# Feeder_1U.net
KiCad netlist of a schematic drawn in Altium Designer
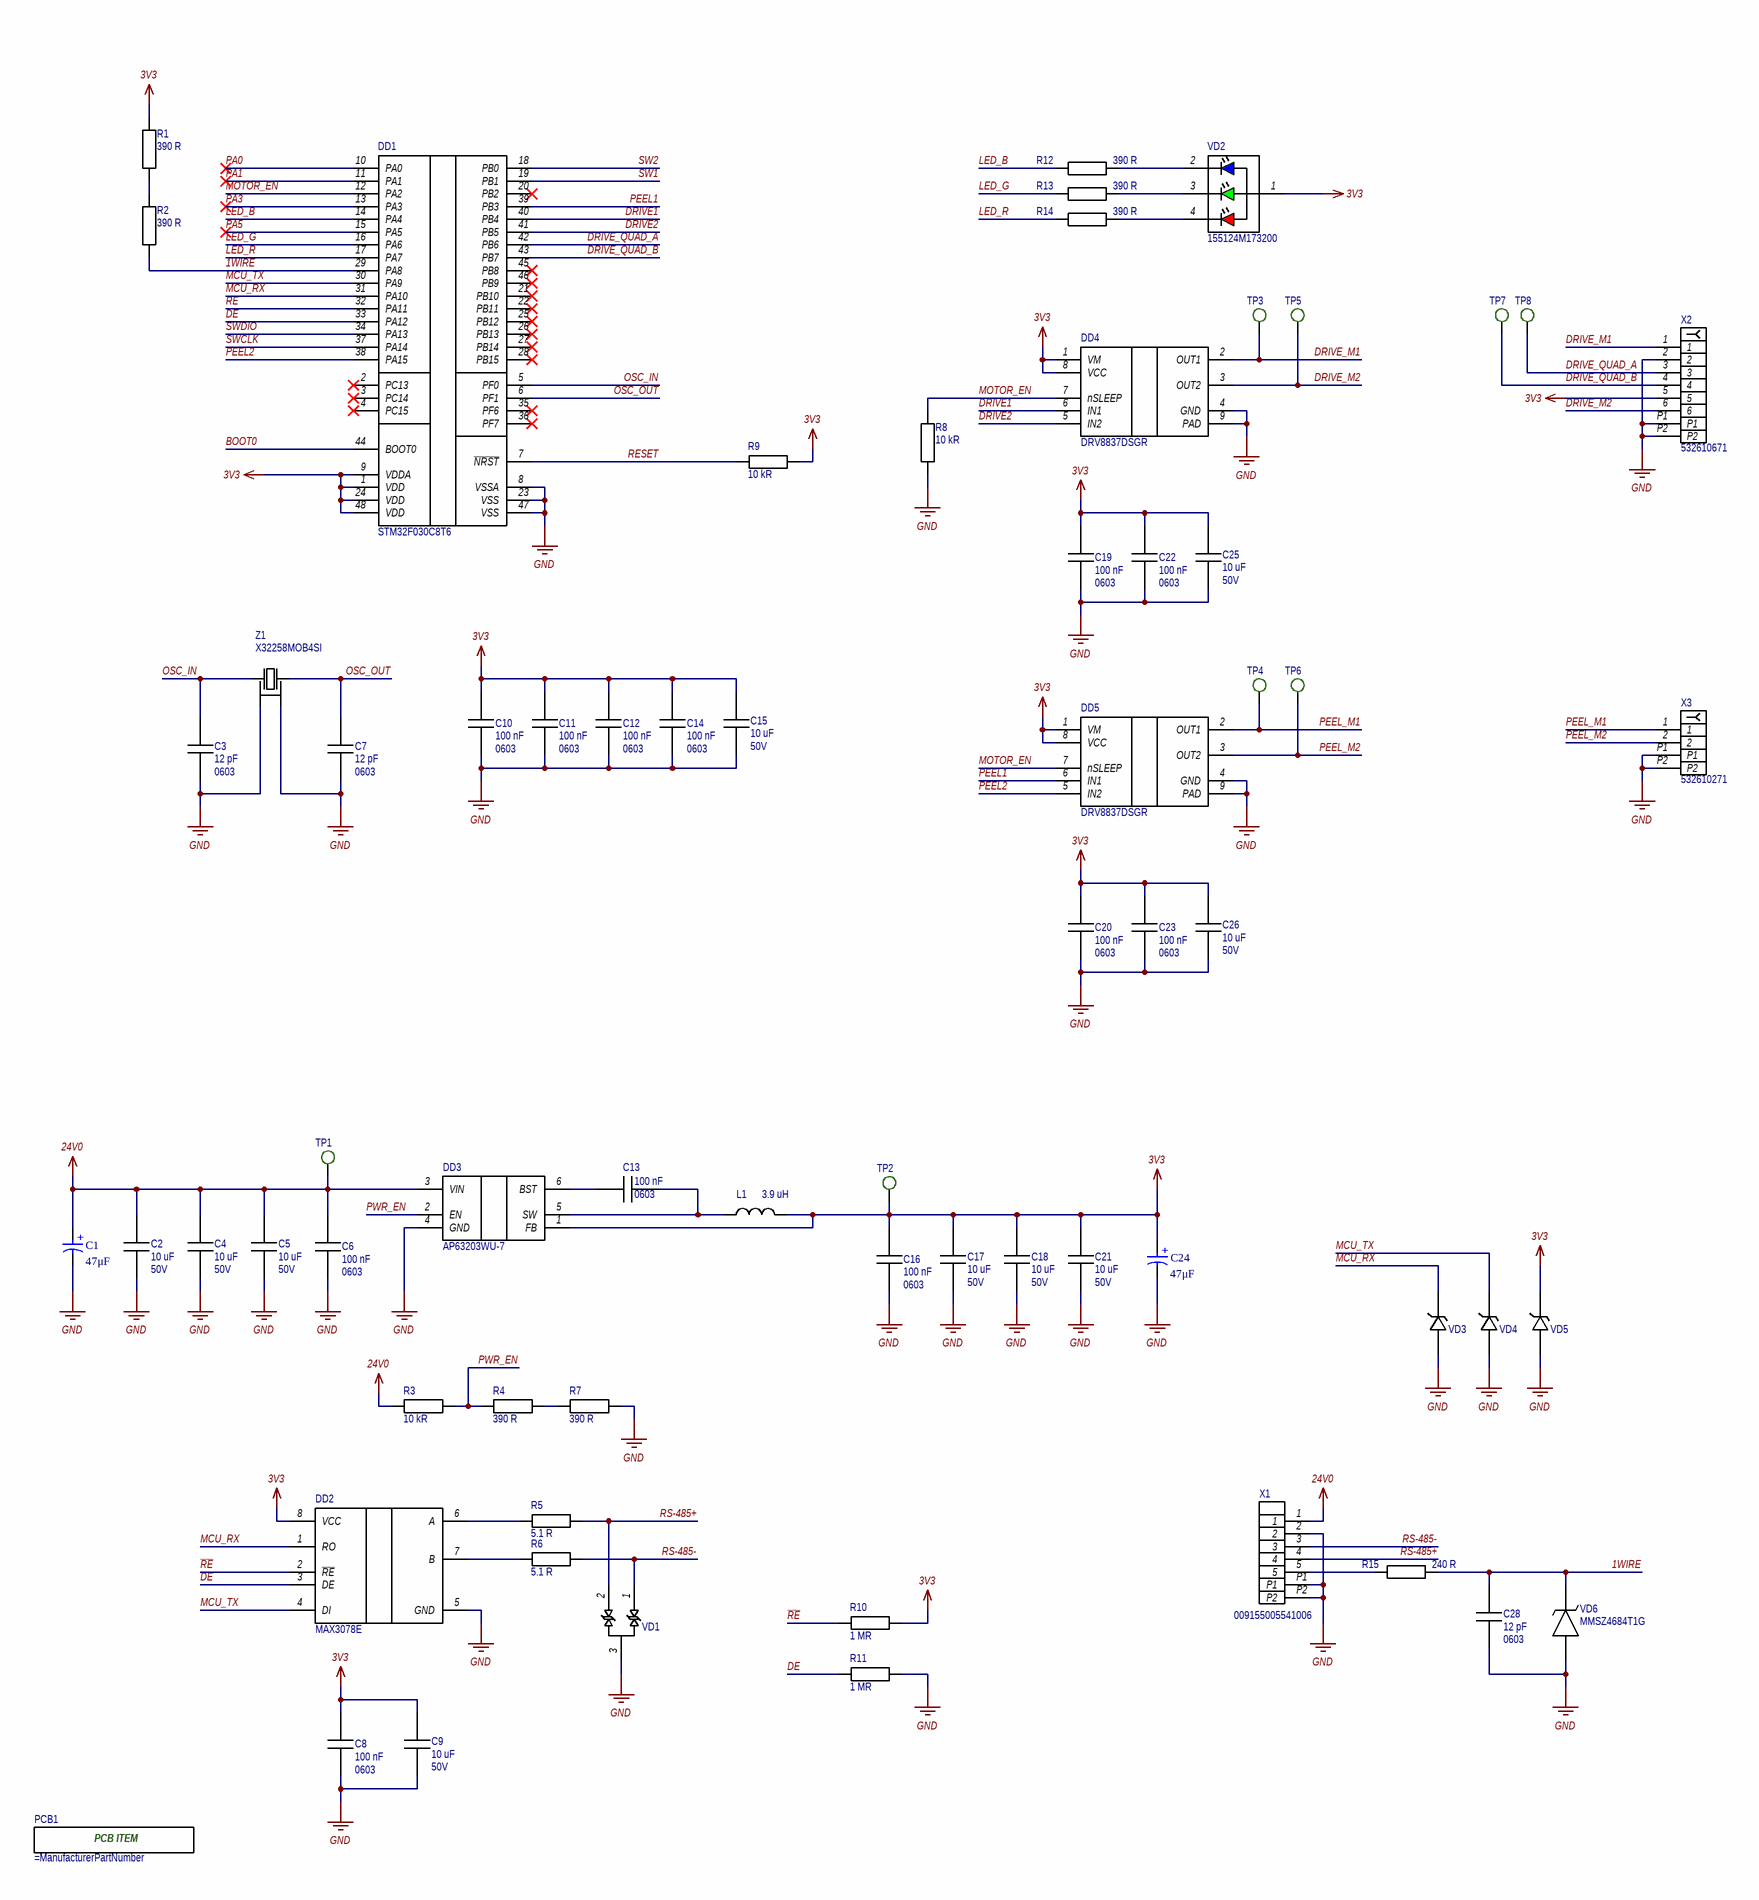
[diagram p0: Feeder_1U.SchDoc, left]
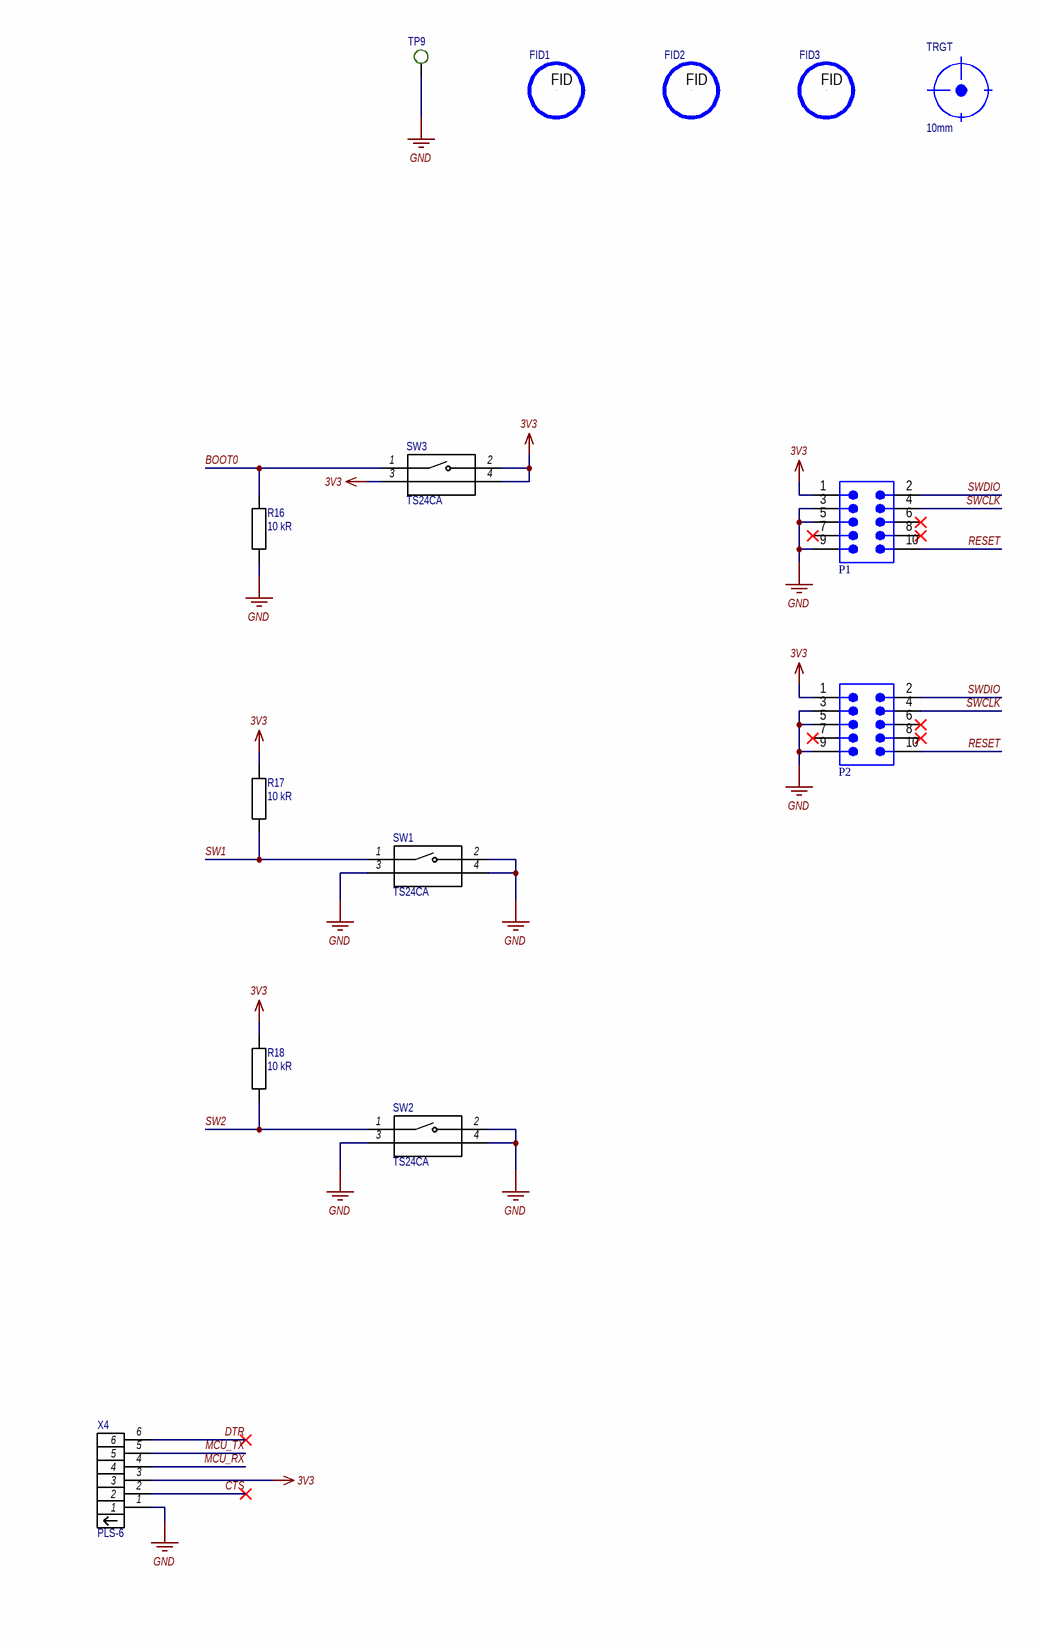
[diagram p1: Feeder_1U.SchDoc, right]

(export (version "E")
  (design (tool "Eeschema 10.0.6"))
  (components
    (comp (ref "C1")
      (value "47μF")
      (footprint "WCAP-ASLI_D6.3H7.7")
      (description "WCAP-ASLI Aluminum Electrolytic Capacitor, V-Chip, SMT, 6.3mm x 7.7mm, 47μF, 50V")
      (fields
        (field (name "MANUFACTURER PART NUMBER") "865080645012")
        (field (name "MANUFACTURER") "Wurth Elektronik")
      )
      (libsource (lib "Altium_WCAP-ASLI (rev25a)") (part "865080645012"))
    )
    (comp (ref "C2")
      (value "10 uF")
      (footprint "C_1206")
      (description "C1206 10uF X7R 50V")
      (fields
        (field (name "TOLERANCE") "±10%")
        (field (name "MANUFACTURERPARTNUMBER") "CL31B106KBHNNNE")
        (field (name "POWER/VOLTAGE") "50V")
      )
      (libsource (lib "AVERLIB_GENERAL") (part "CL31B106KBHNNNE"))
    )
    (comp (ref "C3")
      (value "12 pF")
      (footprint "C_0603")
      (description "C0603 12pF 50V")
      (fields
        (field (name "TOLERANCE") "±5%")
        (field (name "MANUFACTURERPARTNUMBER") "CC0603JRNPO9BN120")
        (field (name "КОРПУС") "0603")
      )
      (libsource (lib "AVERLIB_GENERAL") (part "CC0603JRNPO9BN120"))
    )
    (comp (ref "C4")
      (value "10 uF")
      (footprint "C_1206")
      (description "C1206 10uF X7R 50V")
      (fields
        (field (name "TOLERANCE") "±10%")
        (field (name "MANUFACTURERPARTNUMBER") "CL31B106KBHNNNE")
        (field (name "POWER/VOLTAGE") "50V")
      )
      (libsource (lib "AVERLIB_GENERAL") (part "CL31B106KBHNNNE"))
    )
    (comp (ref "C5")
      (value "10 uF")
      (footprint "C_1206")
      (description "C1206 10uF X7R 50V")
      (fields
        (field (name "TOLERANCE") "±10%")
        (field (name "MANUFACTURERPARTNUMBER") "CL31B106KBHNNNE")
        (field (name "POWER/VOLTAGE") "50V")
      )
      (libsource (lib "AVERLIB_GENERAL") (part "CL31B106KBHNNNE"))
    )
    (comp (ref "C6")
      (value "100 nF")
      (footprint "C_0603")
      (description "C0603 100nF X7R ±10% 50V")
      (fields
        (field (name "TOLERANCE") "10%")
        (field (name "MANUFACTURERPARTNUMBER") "CC0603KRX7R9BB104")
        (field (name "КОРПУС") "0603")
      )
      (libsource (lib "AVERLIB_GENERAL") (part "CC0603KRX7R9BB104"))
    )
    (comp (ref "C7")
      (value "12 pF")
      (footprint "C_0603")
      (description "C0603 12pF 50V")
      (fields
        (field (name "TOLERANCE") "±5%")
        (field (name "MANUFACTURERPARTNUMBER") "CC0603JRNPO9BN120")
        (field (name "КОРПУС") "0603")
      )
      (libsource (lib "AVERLIB_GENERAL") (part "CC0603JRNPO9BN120"))
    )
    (comp (ref "C8")
      (value "100 nF")
      (footprint "C_0603")
      (description "C0603 100nF X7R ±10% 50V")
      (fields
        (field (name "TOLERANCE") "10%")
        (field (name "MANUFACTURERPARTNUMBER") "CC0603KRX7R9BB104")
        (field (name "КОРПУС") "0603")
      )
      (libsource (lib "AVERLIB_GENERAL") (part "CC0603KRX7R9BB104"))
    )
    (comp (ref "C9")
      (value "10 uF")
      (footprint "C_1206")
      (description "C1206 10uF X7R 50V")
      (fields
        (field (name "TOLERANCE") "±10%")
        (field (name "MANUFACTURERPARTNUMBER") "CL31B106KBHNNNE")
        (field (name "POWER/VOLTAGE") "50V")
      )
      (libsource (lib "AVERLIB_GENERAL") (part "CL31B106KBHNNNE"))
    )
    (comp (ref "C10")
      (value "100 nF")
      (footprint "C_0603")
      (description "C0603 100nF X7R ±10% 50V")
      (fields
        (field (name "TOLERANCE") "10%")
        (field (name "MANUFACTURERPARTNUMBER") "CC0603KRX7R9BB104")
        (field (name "КОРПУС") "0603")
      )
      (libsource (lib "AVERLIB_GENERAL") (part "CC0603KRX7R9BB104"))
    )
    (comp (ref "C11")
      (value "100 nF")
      (footprint "C_0603")
      (description "C0603 100nF X7R ±10% 50V")
      (fields
        (field (name "TOLERANCE") "10%")
        (field (name "MANUFACTURERPARTNUMBER") "CC0603KRX7R9BB104")
        (field (name "КОРПУС") "0603")
      )
      (libsource (lib "AVERLIB_GENERAL") (part "CC0603KRX7R9BB104"))
    )
    (comp (ref "C12")
      (value "100 nF")
      (footprint "C_0603")
      (description "C0603 100nF X7R ±10% 50V")
      (fields
        (field (name "TOLERANCE") "10%")
        (field (name "MANUFACTURERPARTNUMBER") "CC0603KRX7R9BB104")
        (field (name "КОРПУС") "0603")
      )
      (libsource (lib "AVERLIB_GENERAL") (part "CC0603KRX7R9BB104"))
    )
    (comp (ref "C13")
      (value "100 nF")
      (footprint "C_0603")
      (description "C0603 100nF X7R ±10% 50V")
      (fields
        (field (name "TOLERANCE") "10%")
        (field (name "MANUFACTURERPARTNUMBER") "CC0603KRX7R9BB104")
        (field (name "КОРПУС") "0603")
      )
      (libsource (lib "AVERLIB_GENERAL") (part "CC0603KRX7R9BB104"))
    )
    (comp (ref "C14")
      (value "100 nF")
      (footprint "C_0603")
      (description "C0603 100nF X7R ±10% 50V")
      (fields
        (field (name "TOLERANCE") "10%")
        (field (name "MANUFACTURERPARTNUMBER") "CC0603KRX7R9BB104")
        (field (name "КОРПУС") "0603")
      )
      (libsource (lib "AVERLIB_GENERAL") (part "CC0603KRX7R9BB104"))
    )
    (comp (ref "C15")
      (value "10 uF")
      (footprint "C_1206")
      (description "C1206 10uF X7R 50V")
      (fields
        (field (name "TOLERANCE") "±10%")
        (field (name "MANUFACTURERPARTNUMBER") "CL31B106KBHNNNE")
        (field (name "POWER/VOLTAGE") "50V")
      )
      (libsource (lib "AVERLIB_GENERAL") (part "CL31B106KBHNNNE"))
    )
    (comp (ref "C16")
      (value "100 nF")
      (footprint "C_0603")
      (description "C0603 100nF X7R ±10% 50V")
      (fields
        (field (name "TOLERANCE") "10%")
        (field (name "MANUFACTURERPARTNUMBER") "CC0603KRX7R9BB104")
        (field (name "КОРПУС") "0603")
      )
      (libsource (lib "AVERLIB_GENERAL") (part "CC0603KRX7R9BB104"))
    )
    (comp (ref "C17")
      (value "10 uF")
      (footprint "C_1206")
      (description "C1206 10uF X7R 50V")
      (fields
        (field (name "TOLERANCE") "±10%")
        (field (name "MANUFACTURERPARTNUMBER") "CL31B106KBHNNNE")
        (field (name "POWER/VOLTAGE") "50V")
      )
      (libsource (lib "AVERLIB_GENERAL") (part "CL31B106KBHNNNE"))
    )
    (comp (ref "C18")
      (value "10 uF")
      (footprint "C_1206")
      (description "C1206 10uF X7R 50V")
      (fields
        (field (name "TOLERANCE") "±10%")
        (field (name "MANUFACTURERPARTNUMBER") "CL31B106KBHNNNE")
        (field (name "POWER/VOLTAGE") "50V")
      )
      (libsource (lib "AVERLIB_GENERAL") (part "CL31B106KBHNNNE"))
    )
    (comp (ref "C19")
      (value "100 nF")
      (footprint "C_0603")
      (description "C0603 100nF X7R ±10% 50V")
      (fields
        (field (name "TOLERANCE") "10%")
        (field (name "MANUFACTURERPARTNUMBER") "CC0603KRX7R9BB104")
        (field (name "КОРПУС") "0603")
      )
      (libsource (lib "AVERLIB_GENERAL") (part "CC0603KRX7R9BB104"))
    )
    (comp (ref "C20")
      (value "100 nF")
      (footprint "C_0603")
      (description "C0603 100nF X7R ±10% 50V")
      (fields
        (field (name "TOLERANCE") "10%")
        (field (name "MANUFACTURERPARTNUMBER") "CC0603KRX7R9BB104")
        (field (name "КОРПУС") "0603")
      )
      (libsource (lib "AVERLIB_GENERAL") (part "CC0603KRX7R9BB104"))
    )
    (comp (ref "C21")
      (value "10 uF")
      (footprint "C_1206")
      (description "C1206 10uF X7R 50V")
      (fields
        (field (name "TOLERANCE") "±10%")
        (field (name "MANUFACTURERPARTNUMBER") "CL31B106KBHNNNE")
        (field (name "POWER/VOLTAGE") "50V")
      )
      (libsource (lib "AVERLIB_GENERAL") (part "CL31B106KBHNNNE"))
    )
    (comp (ref "C22")
      (value "100 nF")
      (footprint "C_0603")
      (description "C0603 100nF X7R ±10% 50V")
      (fields
        (field (name "TOLERANCE") "10%")
        (field (name "MANUFACTURERPARTNUMBER") "CC0603KRX7R9BB104")
        (field (name "КОРПУС") "0603")
      )
      (libsource (lib "AVERLIB_GENERAL") (part "CC0603KRX7R9BB104"))
    )
    (comp (ref "C23")
      (value "100 nF")
      (footprint "C_0603")
      (description "C0603 100nF X7R ±10% 50V")
      (fields
        (field (name "TOLERANCE") "10%")
        (field (name "MANUFACTURERPARTNUMBER") "CC0603KRX7R9BB104")
        (field (name "КОРПУС") "0603")
      )
      (libsource (lib "AVERLIB_GENERAL") (part "CC0603KRX7R9BB104"))
    )
    (comp (ref "C24")
      (value "47μF")
      (footprint "WCAP-ASLI_D6.3H7.7")
      (description "WCAP-ASLI Aluminum Electrolytic Capacitor, V-Chip, SMT, 6.3mm x 7.7mm, 47μF, 50V")
      (fields
        (field (name "MANUFACTURER PART NUMBER") "865080645012")
        (field (name "MANUFACTURER") "Wurth Elektronik")
      )
      (libsource (lib "Altium_WCAP-ASLI (rev25a)") (part "865080645012"))
    )
    (comp (ref "C25")
      (value "10 uF")
      (footprint "C_1206")
      (description "C1206 10uF X7R 50V")
      (fields
        (field (name "TOLERANCE") "±10%")
        (field (name "MANUFACTURERPARTNUMBER") "CL31B106KBHNNNE")
        (field (name "POWER/VOLTAGE") "50V")
      )
      (libsource (lib "AVERLIB_GENERAL") (part "CL31B106KBHNNNE"))
    )
    (comp (ref "C26")
      (value "10 uF")
      (footprint "C_1206")
      (description "C1206 10uF X7R 50V")
      (fields
        (field (name "TOLERANCE") "±10%")
        (field (name "MANUFACTURERPARTNUMBER") "CL31B106KBHNNNE")
        (field (name "POWER/VOLTAGE") "50V")
      )
      (libsource (lib "AVERLIB_GENERAL") (part "CL31B106KBHNNNE"))
    )
    (comp (ref "C28")
      (value "12 pF")
      (footprint "C_0603")
      (description "C0603 12pF 50V")
      (fields
        (field (name "TOLERANCE") "±5%")
        (field (name "MANUFACTURERPARTNUMBER") "CC0603JRNPO9BN120")
        (field (name "КОРПУС") "0603")
      )
      (libsource (lib "AVERLIB_GENERAL") (part "CC0603JRNPO9BN120"))
    )
    (comp (ref "DD1")
      (value "STM32F030C8T6")
      (footprint "QFP-48")
      (description "MCU STM32 ARM Cortex-M0 32Bit 48MHz")
      (fields (field (name "MANUFACTURER") "STM"))
      (libsource (lib "AVERLIB_GENERAL") (part "STM32F030C8T6"))
    )
    (comp (ref "DD2")
      (value "MAX3078E")
      (footprint "SOP8")
      (description "RS-485 Line Driver and Receiver")
      (fields (field (name "MANUFACTURERPARTNUMBER") "MAX3078EESA+T") (field (name "MANUFACTURER") "Maxim"))
      (libsource (lib "AVERLIB_GENERAL") (part "MAX3078E"))
    )
    (comp (ref "DD3")
      (value "AP63203WU-7")
      (footprint "TSOT-23-6")
      (description "DC-DC Stepdown Fixed 2A 3.3V")
      (fields (field (name "MANUFACTURER") "Diodes"))
      (libsource (lib "AVERLIB_GENERAL") (part "AP63203WU-7"))
    )
    (comp (ref "DD4")
      (value "DRV8837DSGR")
      (footprint "WSON-8")
      (description "Motor Driver 1.8A")
      (fields (field (name "MANUFACTURER") "TI"))
      (libsource (lib "AVERLIB_GENERAL") (part "DRV8837DSGR"))
    )
    (comp (ref "DD5")
      (value "DRV8837DSGR")
      (footprint "WSON-8")
      (description "Motor Driver 1.8A")
      (fields (field (name "MANUFACTURER") "TI"))
      (libsource (lib "AVERLIB_GENERAL") (part "DRV8837DSGR"))
    )
    (comp (ref "FID1")
      (value "FID")
      (footprint "FIDUCIAL")
      (libsource (lib "AVERLIB_GENERAL") (part "FIDUCIAL"))
    )
    (comp (ref "FID2")
      (value "FID")
      (footprint "FIDUCIAL")
      (libsource (lib "AVERLIB_GENERAL") (part "FIDUCIAL"))
    )
    (comp (ref "FID3")
      (value "FID")
      (footprint "FIDUCIAL")
      (libsource (lib "AVERLIB_GENERAL") (part "FIDUCIAL"))
    )
    (comp (ref "L1")
      (value "3.9 uH")
      (footprint "IND_SDR0805")
      (description "L 3.9uH  4.4А")
      (fields (field (name "TOLERANCE") "±20%") (field (name "MANUFACTURERPARTNUMBER") "SDR0805-3R9ML"))
      (libsource (lib "AVERLIB_GENERAL") (part "SDR0805-3R9ML"))
    )
    (comp (ref "P1")
      (value "62101021021")
      (footprint "62101021021")
      (description "WR-PHD Pin Header, SMT, Vertical, pitch 1.27mm, 2 Row, 10P")
      (fields (field (name "MANUFACTURER") "Wurth Elektronik"))
      (libsource (lib "Altium_WR-PHD (rev24a)") (part "62101021021"))
    )
    (comp (ref "P2")
      (value "62101021021")
      (footprint "62101021021")
      (description "WR-PHD Pin Header, SMT, Vertical, pitch 1.27mm, 2 Row, 10P")
      (fields (field (name "MANUFACTURER") "Wurth Elektronik"))
      (libsource (lib "Altium_WR-PHD (rev24a)") (part "62101021021"))
    )
    (comp (ref "PCB1")
      (value "~")
      (description "!PCB")
      (fields (field (name "MANUFACTURER") "NOVA"))
      (libsource (lib "AVERLIB_GENERAL") (part "!PCB"))
    )
    (comp (ref "R1")
      (value "390 R")
      (footprint "R_0603")
      (description "R0603 390±1% 50V")
      (fields (field (name "TOLERANCE") "±1%") (field (name "MANUFACTURERPARTNUMBER") "RC0603FR-07390RL"))
      (libsource (lib "AVERLIB_GENERAL") (part "RC0603FR-07390RL"))
    )
    (comp (ref "R2")
      (value "390 R")
      (footprint "R_0603")
      (description "R0603 390±1% 50V")
      (fields (field (name "TOLERANCE") "±1%") (field (name "MANUFACTURERPARTNUMBER") "RC0603FR-07390RL"))
      (libsource (lib "AVERLIB_GENERAL") (part "RC0603FR-07390RL"))
    )
    (comp (ref "R3")
      (value "10 kR")
      (footprint "R_0603")
      (description "R0603 10k±1% 50V")
      (fields (field (name "TOLERANCE") "±1%") (field (name "MANUFACTURERPARTNUMBER") "RC0603FR-0710KL"))
      (libsource (lib "AVERLIB_GENERAL") (part "RC0603FR-0710KL"))
    )
    (comp (ref "R4")
      (value "390 R")
      (footprint "R_0603")
      (description "R0603 390±1% 50V")
      (fields (field (name "TOLERANCE") "±1%") (field (name "MANUFACTURERPARTNUMBER") "RC0603FR-07390RL"))
      (libsource (lib "AVERLIB_GENERAL") (part "RC0603FR-07390RL"))
    )
    (comp (ref "R5")
      (value "5.1 R")
      (footprint "R_0603")
      (description "R0603 5R1±1% 50V")
      (fields (field (name "TOLERANCE") "±1%") (field (name "MANUFACTURERPARTNUMBER") "RC0603FR-075R1L"))
      (libsource (lib "AVERLIB_GENERAL") (part "RC0603FR-075R1L"))
    )
    (comp (ref "R6")
      (value "5.1 R")
      (footprint "R_0603")
      (description "R0603 5R1±1% 50V")
      (fields (field (name "TOLERANCE") "±1%") (field (name "MANUFACTURERPARTNUMBER") "RC0603FR-075R1L"))
      (libsource (lib "AVERLIB_GENERAL") (part "RC0603FR-075R1L"))
    )
    (comp (ref "R7")
      (value "390 R")
      (footprint "R_0603")
      (description "R0603 390±1% 50V")
      (fields (field (name "TOLERANCE") "±1%") (field (name "MANUFACTURERPARTNUMBER") "RC0603FR-07390RL"))
      (libsource (lib "AVERLIB_GENERAL") (part "RC0603FR-07390RL"))
    )
    (comp (ref "R8")
      (value "10 kR")
      (footprint "R_0603")
      (description "R0603 10k±1% 50V")
      (fields (field (name "TOLERANCE") "±1%") (field (name "MANUFACTURERPARTNUMBER") "RC0603FR-0710KL"))
      (libsource (lib "AVERLIB_GENERAL") (part "RC0603FR-0710KL"))
    )
    (comp (ref "R9")
      (value "10 kR")
      (footprint "R_0603")
      (description "R0603 10k±1% 50V")
      (fields (field (name "TOLERANCE") "±1%") (field (name "MANUFACTURERPARTNUMBER") "RC0603FR-0710KL"))
      (libsource (lib "AVERLIB_GENERAL") (part "RC0603FR-0710KL"))
    )
    (comp (ref "R10")
      (value "1 MR")
      (footprint "R_0603")
      (description "R0603 1M±1% 50V")
      (fields (field (name "TOLERANCE") "±1%") (field (name "MANUFACTURERPARTNUMBER") "RC0603FR-071ML"))
      (libsource (lib "AVERLIB_GENERAL") (part "RC0603FR-071ML"))
    )
    (comp (ref "R11")
      (value "1 MR")
      (footprint "R_0603")
      (description "R0603 1M±1% 50V")
      (fields (field (name "TOLERANCE") "±1%") (field (name "MANUFACTURERPARTNUMBER") "RC0603FR-071ML"))
      (libsource (lib "AVERLIB_GENERAL") (part "RC0603FR-071ML"))
    )
    (comp (ref "R12")
      (value "390 R")
      (footprint "R_0603")
      (description "R0603 390±1% 50V")
      (fields (field (name "TOLERANCE") "±1%") (field (name "MANUFACTURERPARTNUMBER") "RC0603FR-07390RL"))
      (libsource (lib "AVERLIB_GENERAL") (part "RC0603FR-07390RL"))
    )
    (comp (ref "R13")
      (value "390 R")
      (footprint "R_0603")
      (description "R0603 390±1% 50V")
      (fields (field (name "TOLERANCE") "±1%") (field (name "MANUFACTURERPARTNUMBER") "RC0603FR-07390RL"))
      (libsource (lib "AVERLIB_GENERAL") (part "RC0603FR-07390RL"))
    )
    (comp (ref "R14")
      (value "390 R")
      (footprint "R_0603")
      (description "R0603 390±1% 50V")
      (fields (field (name "TOLERANCE") "±1%") (field (name "MANUFACTURERPARTNUMBER") "RC0603FR-07390RL"))
      (libsource (lib "AVERLIB_GENERAL") (part "RC0603FR-07390RL"))
    )
    (comp (ref "R15")
      (value "240 R")
      (footprint "R_0603")
      (description "R0603 240±1% 50V")
      (fields (field (name "TOLERANCE") "±1%") (field (name "MANUFACTURERPARTNUMBER") "RC0603FR-07240RL"))
      (libsource (lib "AVERLIB_GENERAL") (part "RC0603FR-07240RL"))
    )
    (comp (ref "R16")
      (value "10 kR")
      (footprint "R_0603")
      (description "R0603 10k±1% 50V")
      (fields (field (name "TOLERANCE") "±1%") (field (name "MANUFACTURERPARTNUMBER") "RC0603FR-0710KL"))
      (libsource (lib "AVERLIB_GENERAL") (part "RC0603FR-0710KL"))
    )
    (comp (ref "R17")
      (value "10 kR")
      (footprint "R_0603")
      (description "R0603 10k±1% 50V")
      (fields (field (name "TOLERANCE") "±1%") (field (name "MANUFACTURERPARTNUMBER") "RC0603FR-0710KL"))
      (libsource (lib "AVERLIB_GENERAL") (part "RC0603FR-0710KL"))
    )
    (comp (ref "R18")
      (value "10 kR")
      (footprint "R_0603")
      (description "R0603 10k±1% 50V")
      (fields (field (name "TOLERANCE") "±1%") (field (name "MANUFACTURERPARTNUMBER") "RC0603FR-0710KL"))
      (libsource (lib "AVERLIB_GENERAL") (part "RC0603FR-0710KL"))
    )
    (comp (ref "SW1")
      (value "TS24CA")
      (footprint "TS24CA")
      (description "Switch Tacticle (button) 4.7x1.9mm angle")
      (fields (field (name "MANUFACTURER") "Shou HAN"))
      (libsource (lib "AVERLIB_GENERAL") (part "TS24CA"))
    )
    (comp (ref "SW2")
      (value "TS24CA")
      (footprint "TS24CA")
      (description "Switch Tacticle (button) 4.7x1.9mm angle")
      (fields (field (name "MANUFACTURER") "Shou HAN"))
      (libsource (lib "AVERLIB_GENERAL") (part "TS24CA"))
    )
    (comp (ref "SW3")
      (value "TS24CA")
      (footprint "TS24CA")
      (description "Switch Tacticle (button) 4.7x1.9mm angle")
      (fields (field (name "MANUFACTURER") "Shou HAN"))
      (libsource (lib "AVERLIB_GENERAL") (part "TS24CA"))
    )
    (comp (ref "TP1")
      (value "*")
      (footprint "TEST POINT ROUND")
      (description "Test Point")
      (libsource (lib "AVERLIB_GENERAL") (part "TEST POINT"))
    )
    (comp (ref "TP2")
      (value "*")
      (footprint "TEST POINT ROUND")
      (description "Test Point")
      (libsource (lib "AVERLIB_GENERAL") (part "TEST POINT"))
    )
    (comp (ref "TP3")
      (value "*")
      (footprint "TEST POINT ROUND")
      (description "Test Point")
      (libsource (lib "AVERLIB_GENERAL") (part "TEST POINT"))
    )
    (comp (ref "TP4")
      (value "*")
      (footprint "TEST POINT ROUND")
      (description "Test Point")
      (libsource (lib "AVERLIB_GENERAL") (part "TEST POINT"))
    )
    (comp (ref "TP5")
      (value "*")
      (footprint "TEST POINT ROUND")
      (description "Test Point")
      (libsource (lib "AVERLIB_GENERAL") (part "TEST POINT"))
    )
    (comp (ref "TP6")
      (value "*")
      (footprint "TEST POINT ROUND")
      (description "Test Point")
      (libsource (lib "AVERLIB_GENERAL") (part "TEST POINT"))
    )
    (comp (ref "TP7")
      (value "*")
      (footprint "TEST POINT ROUND")
      (description "Test Point")
      (libsource (lib "AVERLIB_GENERAL") (part "TEST POINT"))
    )
    (comp (ref "TP8")
      (value "*")
      (footprint "TEST POINT ROUND")
      (description "Test Point")
      (libsource (lib "AVERLIB_GENERAL") (part "TEST POINT"))
    )
    (comp (ref "TP9")
      (value "*")
      (footprint "TEST POINT ROUND")
      (description "Test Point")
      (libsource (lib "AVERLIB_GENERAL") (part "TEST POINT"))
    )
    (comp (ref "TRGT")
      (value "10mm")
      (footprint "PrinterTarget")
      (description "SMD Printer calibration PCB thikness target")
      (libsource (lib "AVERLIB_GENERAL") (part "PrinterTarget_10mm"))
    )
    (comp (ref "VD1")
      (value "SM712")
      (footprint "SOT23")
      (description "ESD Suppressor Diode TVS RS485")
      (fields (field (name "MANUFACTURER") "TECH PUBLIC"))
      (libsource (lib "AVERLIB_GENERAL") (part "SM712"))
    )
    (comp (ref "VD2")
      (value "155124M173200")
      (footprint "LED_3210_RGB_SIDE")
      (description "LED RGB 3210 ANGLE")
      (fields (field (name "MANUFACTURER") "Wurth Elec") (field (name "ANALOGPARTNUMBER") "MHS110FRGBCT"))
      (libsource (lib "AVERLIB_GENERAL") (part "155124M173200"))
    )
    (comp (ref "VD3")
      (value "PESD3V3S1UL,315")
      (footprint "DFN1006-2_(SOD882)")
      (description "ESD Suppressor Diode TVS 3V3")
      (fields (field (name "MANUFACTURER") "Nexperia"))
      (libsource (lib "AVERLIB_GENERAL") (part "PESD3V3S1UL,315"))
    )
    (comp (ref "VD4")
      (value "PESD3V3S1UL,315")
      (footprint "DFN1006-2_(SOD882)")
      (description "ESD Suppressor Diode TVS 3V3")
      (fields (field (name "MANUFACTURER") "Nexperia"))
      (libsource (lib "AVERLIB_GENERAL") (part "PESD3V3S1UL,315"))
    )
    (comp (ref "VD5")
      (value "PESD3V3S1UL,315")
      (footprint "DFN1006-2_(SOD882)")
      (description "ESD Suppressor Diode TVS 3V3")
      (fields (field (name "MANUFACTURER") "Nexperia"))
      (libsource (lib "AVERLIB_GENERAL") (part "PESD3V3S1UL,315"))
    )
    (comp (ref "VD6")
      (value "MMSZ4684T1G")
      (footprint "SOD-123")
      (description "Zener Diode 3.3V SOD-123")
      (fields (field (name "MANUFACTURER") "onsemi"))
      (libsource (lib "AVERLIB_GENERAL") (part "MMSZ4684T1G"))
    )
    (comp (ref "X1")
      (value "009155005541006")
      (footprint "009155005541006")
      (description "Connector, пружинный контакт для аккумулятора, шаг 2.5мм")
      (fields (field (name "MANUFACTURER") "Kyocera AVX"))
      (libsource (lib "AVERLIB_GENERAL") (part "009155005541006"))
    )
    (comp (ref "X2")
      (value "532610671")
      (footprint "532610671")
      (description "Connector Molex PicoBlade SMD 6pin")
      (fields (field (name "MANUFACTURER") "MOLEX"))
      (libsource (lib "AVERLIB_GENERAL") (part "532610671"))
    )
    (comp (ref "X3")
      (value "532610271")
      (footprint "532610271")
      (description "Connector Molex PicoBlade SMD 2pin")
      (fields (field (name "MANUFACTURER") "MOLEX"))
      (libsource (lib "AVERLIB_GENERAL") (part "532610271"))
    )
    (comp (ref "X4")
      (value "PLS-6")
      (footprint "PLS-6-3D")
      (description "Header, 6-Pin")
      (libsource (lib "AVERLIB_GENERAL") (part "PLS-6"))
    )
    (comp (ref "Z1")
      (value "X32258MOB4SI")
      (footprint "SMD3225")
      (description "Crystal 8MHz 12pF")
      (fields (field (name "TOLERANCE") "±10ppm") (field (name "MANUFACTURER") "YXC Crystal Oscillators"))
      (libsource (lib "AVERLIB_GENERAL") (part "X32258MOB4SI"))
    )
  )
  (nets
    (net (code "1") (name "/1WIRE") (class "Default")
      (node (ref "C28") (pin "1") (pinfunction "1_1") (pintype "passive"))
      (node (ref "DD1") (pin "29") (pinfunction "PA8_29") (pintype "passive"))
      (node (ref "R15") (pin "2") (pinfunction "2_2") (pintype "passive"))
      (node (ref "R2") (pin "2") (pinfunction "2_2") (pintype "passive"))
      (node (ref "VD6") (pin "1") (pinfunction "K_1") (pintype "passive"))
    )
    (net (code "2") (name "/BOOT0") (class "Default")
      (node (ref "DD1") (pin "44") (pinfunction "BOOT0_44") (pintype "passive"))
      (node (ref "R16") (pin "2") (pinfunction "2_2") (pintype "passive"))
      (node (ref "SW3") (pin "1") (pinfunction "COM_1_1") (pintype "passive"))
    )
    (net (code "3") (name "/CTS") (class "Default")
      (node (ref "X4") (pin "2") (pinfunction "2_2") (pintype "passive+no_connect"))
    )
    (net (code "4") (name "/DE") (class "Default")
      (node (ref "DD1") (pin "33") (pinfunction "PA12_33") (pintype "passive"))
      (node (ref "DD2") (pin "3") (pinfunction "DE_3") (pintype "passive"))
      (node (ref "R11") (pin "1") (pinfunction "1_1") (pintype "passive"))
    )
    (net (code "5") (name "/DRIVE1") (class "Default")
      (node (ref "DD1") (pin "40") (pinfunction "PB4_40") (pintype "passive"))
      (node (ref "DD4") (pin "6") (pinfunction "IN1_6") (pintype "passive"))
    )
    (net (code "6") (name "/DRIVE2") (class "Default")
      (node (ref "DD1") (pin "41") (pinfunction "PB5_41") (pintype "passive"))
      (node (ref "DD4") (pin "5") (pinfunction "IN2_5") (pintype "passive"))
    )
    (net (code "7") (name "/DRIVE_M1") (class "Default")
      (node (ref "DD4") (pin "2") (pinfunction "OUT1_2") (pintype "passive"))
      (node (ref "TP3") (pin "1") (pinfunction "1_1") (pintype "passive"))
      (node (ref "X2") (pin "1") (pinfunction "1_1") (pintype "passive"))
    )
    (net (code "8") (name "/DRIVE_M2") (class "Default")
      (node (ref "DD4") (pin "3") (pinfunction "OUT2_3") (pintype "passive"))
      (node (ref "TP5") (pin "1") (pinfunction "1_1") (pintype "passive"))
      (node (ref "X2") (pin "6") (pinfunction "6_6") (pintype "passive"))
    )
    (net (code "9") (name "/DRIVE_QUAD_A") (class "Default")
      (node (ref "DD1") (pin "42") (pinfunction "PB6_42") (pintype "passive"))
      (node (ref "TP8") (pin "1") (pinfunction "1_1") (pintype "passive"))
      (node (ref "X2") (pin "3") (pinfunction "3_3") (pintype "passive"))
    )
    (net (code "10") (name "/DRIVE_QUAD_B") (class "Default")
      (node (ref "DD1") (pin "43") (pinfunction "PB7_43") (pintype "passive"))
      (node (ref "TP7") (pin "1") (pinfunction "1_1") (pintype "passive"))
      (node (ref "X2") (pin "4") (pinfunction "4_4") (pintype "passive"))
    )
    (net (code "11") (name "/DTR") (class "Default")
      (node (ref "X4") (pin "6") (pinfunction "6_6") (pintype "passive+no_connect"))
    )
    (net (code "12") (name "/LED_B") (class "Default")
      (node (ref "DD1") (pin "14") (pinfunction "PA4_14") (pintype "passive"))
      (node (ref "R12") (pin "1") (pinfunction "1_1") (pintype "passive"))
    )
    (net (code "13") (name "/LED_G") (class "Default")
      (node (ref "DD1") (pin "16") (pinfunction "PA6_16") (pintype "passive"))
      (node (ref "R13") (pin "1") (pinfunction "1_1") (pintype "passive"))
    )
    (net (code "14") (name "/LED_R") (class "Default")
      (node (ref "DD1") (pin "17") (pinfunction "PA7_17") (pintype "passive"))
      (node (ref "R14") (pin "1") (pinfunction "1_1") (pintype "passive"))
    )
    (net (code "15") (name "/MCU_RX") (class "Default")
      (node (ref "DD1") (pin "31") (pinfunction "PA10_31") (pintype "passive"))
      (node (ref "DD2") (pin "1") (pinfunction "RO_1") (pintype "passive"))
      (node (ref "VD3") (pin "1") (pinfunction "1_1") (pintype "passive"))
      (node (ref "X4") (pin "4") (pinfunction "4_4") (pintype "passive"))
    )
    (net (code "16") (name "/MCU_TX") (class "Default")
      (node (ref "DD1") (pin "30") (pinfunction "PA9_30") (pintype "passive"))
      (node (ref "DD2") (pin "4") (pinfunction "DI_4") (pintype "passive"))
      (node (ref "VD4") (pin "1") (pinfunction "1_1") (pintype "passive"))
      (node (ref "X4") (pin "5") (pinfunction "5_5") (pintype "passive"))
    )
    (net (code "17") (name "/MOTOR_EN") (class "Default")
      (node (ref "DD1") (pin "12") (pinfunction "PA2_12") (pintype "passive"))
      (node (ref "DD4") (pin "7") (pinfunction "nSLEEP_7") (pintype "passive"))
      (node (ref "DD5") (pin "7") (pinfunction "nSLEEP_7") (pintype "passive"))
      (node (ref "R8") (pin "1") (pinfunction "1_1") (pintype "passive"))
    )
    (net (code "18") (name "/OSC_IN") (class "Default")
      (node (ref "C3") (pin "1") (pinfunction "1_1") (pintype "passive"))
      (node (ref "DD1") (pin "5") (pinfunction "PF0_5") (pintype "passive"))
      (node (ref "Z1") (pin "1") (pintype "passive"))
    )
    (net (code "19") (name "/OSC_OUT") (class "Default")
      (node (ref "C7") (pin "1") (pinfunction "1_1") (pintype "passive"))
      (node (ref "DD1") (pin "6") (pinfunction "PF1_6") (pintype "passive"))
      (node (ref "Z1") (pin "3") (pintype "passive"))
    )
    (net (code "20") (name "/PA0") (class "Default")
      (node (ref "DD1") (pin "10") (pinfunction "PA0_10") (pintype "passive+no_connect"))
    )
    (net (code "21") (name "/PA1") (class "Default")
      (node (ref "DD1") (pin "11") (pinfunction "PA1_11") (pintype "passive+no_connect"))
    )
    (net (code "22") (name "/PA3") (class "Default")
      (node (ref "DD1") (pin "13") (pinfunction "PA3_13") (pintype "passive+no_connect"))
    )
    (net (code "23") (name "/PA5") (class "Default")
      (node (ref "DD1") (pin "15") (pinfunction "PA5_15") (pintype "passive+no_connect"))
    )
    (net (code "24") (name "/PEEL1") (class "Default")
      (node (ref "DD1") (pin "39") (pinfunction "PB3_39") (pintype "passive"))
      (node (ref "DD5") (pin "6") (pinfunction "IN1_6") (pintype "passive"))
    )
    (net (code "25") (name "/PEEL2") (class "Default")
      (node (ref "DD1") (pin "38") (pinfunction "PA15_38") (pintype "passive"))
      (node (ref "DD5") (pin "5") (pinfunction "IN2_5") (pintype "passive"))
    )
    (net (code "26") (name "/PEEL_M1") (class "Default")
      (node (ref "DD5") (pin "2") (pinfunction "OUT1_2") (pintype "passive"))
      (node (ref "TP4") (pin "1") (pinfunction "1_1") (pintype "passive"))
      (node (ref "X3") (pin "1") (pinfunction "1_1") (pintype "passive"))
    )
    (net (code "27") (name "/PEEL_M2") (class "Default")
      (node (ref "DD5") (pin "3") (pinfunction "OUT2_3") (pintype "passive"))
      (node (ref "TP6") (pin "1") (pinfunction "1_1") (pintype "passive"))
      (node (ref "X3") (pin "2") (pinfunction "2_2") (pintype "passive"))
    )
    (net (code "28") (name "/PWR_EN") (class "Default")
      (node (ref "DD3") (pin "2") (pinfunction "EN_2") (pintype "passive"))
      (node (ref "R3") (pin "2") (pinfunction "2_2") (pintype "passive"))
      (node (ref "R4") (pin "2") (pinfunction "2_2") (pintype "passive"))
    )
    (net (code "29") (name "/RESET") (class "Default")
      (node (ref "DD1") (pin "7") (pinfunction "~{NRST}_7") (pintype "passive"))
      (node (ref "P1") (pin "10") (pinfunction "10_10") (pintype "passive"))
      (node (ref "P2") (pin "10") (pinfunction "10_10") (pintype "passive"))
      (node (ref "R9") (pin "2") (pinfunction "2_2") (pintype "passive"))
    )
    (net (code "30") (name "/RS-485+") (class "Default")
      (node (ref "R5") (pin "2") (pinfunction "2_2") (pintype "passive"))
      (node (ref "VD1") (pin "2") (pinfunction "2_2") (pintype "passive"))
      (node (ref "X1") (pin "4") (pinfunction "4_4") (pintype "passive"))
    )
    (net (code "31") (name "/RS-485-") (class "Default")
      (node (ref "R6") (pin "2") (pinfunction "2_2") (pintype "passive"))
      (node (ref "VD1") (pin "1") (pinfunction "1_1") (pintype "passive"))
      (node (ref "X1") (pin "3") (pinfunction "3_3") (pintype "passive"))
    )
    (net (code "32") (name "/SW1") (class "Default")
      (node (ref "DD1") (pin "19") (pinfunction "PB1_19") (pintype "passive"))
      (node (ref "R17") (pin "1") (pinfunction "1_1") (pintype "passive"))
      (node (ref "SW1") (pin "1") (pinfunction "COM_1_1") (pintype "passive"))
    )
    (net (code "33") (name "/SW2") (class "Default")
      (node (ref "DD1") (pin "18") (pinfunction "PB0_18") (pintype "passive"))
      (node (ref "R18") (pin "1") (pinfunction "1_1") (pintype "passive"))
      (node (ref "SW2") (pin "1") (pinfunction "COM_1_1") (pintype "passive"))
    )
    (net (code "34") (name "/SWCLK") (class "Default")
      (node (ref "DD1") (pin "37") (pinfunction "PA14_37") (pintype "passive"))
      (node (ref "P1") (pin "4") (pinfunction "4_4") (pintype "passive"))
      (node (ref "P2") (pin "4") (pinfunction "4_4") (pintype "passive"))
    )
    (net (code "35") (name "/SWDIO") (class "Default")
      (node (ref "DD1") (pin "34") (pinfunction "PA13_34") (pintype "passive"))
      (node (ref "P1") (pin "2") (pinfunction "2_2") (pintype "passive"))
      (node (ref "P2") (pin "2") (pinfunction "2_2") (pintype "passive"))
    )
    (net (code "36") (name "/~{RE}") (class "Default")
      (node (ref "DD1") (pin "32") (pinfunction "PA11_32") (pintype "passive"))
      (node (ref "DD2") (pin "2") (pinfunction "~{RE}_2") (pintype "passive"))
      (node (ref "R10") (pin "1") (pinfunction "1_1") (pintype "passive"))
    )
    (net (code "37") (name "3V3") (class "Default")
      (node (ref "C10") (pin "2") (pinfunction "2_2") (pintype "passive"))
      (node (ref "C11") (pin "2") (pinfunction "2_2") (pintype "passive"))
      (node (ref "C12") (pin "2") (pinfunction "2_2") (pintype "passive"))
      (node (ref "C14") (pin "2") (pinfunction "2_2") (pintype "passive"))
      (node (ref "C15") (pin "2") (pinfunction "2_2") (pintype "passive"))
      (node (ref "C16") (pin "2") (pinfunction "2_2") (pintype "passive"))
      (node (ref "C17") (pin "2") (pinfunction "2_2") (pintype "passive"))
      (node (ref "C18") (pin "2") (pinfunction "2_2") (pintype "passive"))
      (node (ref "C19") (pin "2") (pinfunction "2_2") (pintype "passive"))
      (node (ref "C20") (pin "2") (pinfunction "2_2") (pintype "passive"))
      (node (ref "C21") (pin "2") (pinfunction "2_2") (pintype "passive"))
      (node (ref "C22") (pin "2") (pinfunction "2_2") (pintype "passive"))
      (node (ref "C23") (pin "2") (pinfunction "2_2") (pintype "passive"))
      (node (ref "C24") (pin "1") (pinfunction "P_1") (pintype "passive"))
      (node (ref "C25") (pin "2") (pinfunction "2_2") (pintype "passive"))
      (node (ref "C26") (pin "2") (pinfunction "2_2") (pintype "passive"))
      (node (ref "C8") (pin "2") (pinfunction "2_2") (pintype "passive"))
      (node (ref "C9") (pin "2") (pinfunction "2_2") (pintype "passive"))
      (node (ref "DD1") (pin "1") (pinfunction "VDD_1") (pintype "passive"))
      (node (ref "DD1") (pin "24") (pinfunction "VDD_24") (pintype "passive"))
      (node (ref "DD1") (pin "48") (pinfunction "VDD_48") (pintype "passive"))
      (node (ref "DD1") (pin "9") (pinfunction "VDDA_9") (pintype "passive"))
      (node (ref "DD2") (pin "8") (pinfunction "VCC_8") (pintype "passive"))
      (node (ref "DD3") (pin "1") (pinfunction "FB_1") (pintype "passive"))
      (node (ref "DD4") (pin "1") (pinfunction "VM_1") (pintype "passive"))
      (node (ref "DD4") (pin "8") (pinfunction "VCC_8") (pintype "passive"))
      (node (ref "DD5") (pin "1") (pinfunction "VM_1") (pintype "passive"))
      (node (ref "DD5") (pin "8") (pinfunction "VCC_8") (pintype "passive"))
      (node (ref "L1") (pin "2") (pinfunction "2_2") (pintype "passive"))
      (node (ref "P1") (pin "1") (pinfunction "1_1") (pintype "passive"))
      (node (ref "P2") (pin "1") (pinfunction "1_1") (pintype "passive"))
      (node (ref "R1") (pin "1") (pinfunction "1_1") (pintype "passive"))
      (node (ref "R10") (pin "2") (pinfunction "2_2") (pintype "passive"))
      (node (ref "R17") (pin "2") (pinfunction "2_2") (pintype "passive"))
      (node (ref "R18") (pin "2") (pinfunction "2_2") (pintype "passive"))
      (node (ref "R9") (pin "1") (pinfunction "1_1") (pintype "passive"))
      (node (ref "SW3") (pin "2") (pinfunction "NO_1_2") (pintype "passive"))
      (node (ref "SW3") (pin "3") (pinfunction "NO_2_3") (pintype "passive"))
      (node (ref "SW3") (pin "4") (pinfunction "NO_3_4") (pintype "passive"))
      (node (ref "TP2") (pin "1") (pinfunction "1_1") (pintype "passive"))
      (node (ref "VD2") (pin "1") (pinfunction "RED_ANODE_1") (pintype "passive"))
      (node (ref "VD5") (pin "1") (pinfunction "1_1") (pintype "passive"))
      (node (ref "X2") (pin "5") (pinfunction "5_5") (pintype "passive"))
      (node (ref "X4") (pin "3") (pinfunction "3_3") (pintype "passive"))
    )
    (net (code "38") (name "24V0") (class "Default")
      (node (ref "C1") (pin "1") (pinfunction "P_1") (pintype "passive"))
      (node (ref "C2") (pin "2") (pinfunction "2_2") (pintype "passive"))
      (node (ref "C4") (pin "2") (pinfunction "2_2") (pintype "passive"))
      (node (ref "C5") (pin "2") (pinfunction "2_2") (pintype "passive"))
      (node (ref "C6") (pin "2") (pinfunction "2_2") (pintype "passive"))
      (node (ref "DD3") (pin "3") (pinfunction "VIN_3") (pintype "power_in"))
      (node (ref "R3") (pin "1") (pinfunction "1_1") (pintype "passive"))
      (node (ref "TP1") (pin "1") (pinfunction "1_1") (pintype "passive"))
      (node (ref "X1") (pin "1") (pinfunction "1_1") (pintype "passive"))
    )
    (net (code "39") (name "GND") (class "Default")
      (node (ref "C1") (pin "2") (pinfunction "N_2") (pintype "passive"))
      (node (ref "C10") (pin "1") (pinfunction "1_1") (pintype "passive"))
      (node (ref "C11") (pin "1") (pinfunction "1_1") (pintype "passive"))
      (node (ref "C12") (pin "1") (pinfunction "1_1") (pintype "passive"))
      (node (ref "C14") (pin "1") (pinfunction "1_1") (pintype "passive"))
      (node (ref "C15") (pin "1") (pinfunction "1_1") (pintype "passive"))
      (node (ref "C16") (pin "1") (pinfunction "1_1") (pintype "passive"))
      (node (ref "C17") (pin "1") (pinfunction "1_1") (pintype "passive"))
      (node (ref "C18") (pin "1") (pinfunction "1_1") (pintype "passive"))
      (node (ref "C19") (pin "1") (pinfunction "1_1") (pintype "passive"))
      (node (ref "C2") (pin "1") (pinfunction "1_1") (pintype "passive"))
      (node (ref "C20") (pin "1") (pinfunction "1_1") (pintype "passive"))
      (node (ref "C21") (pin "1") (pinfunction "1_1") (pintype "passive"))
      (node (ref "C22") (pin "1") (pinfunction "1_1") (pintype "passive"))
      (node (ref "C23") (pin "1") (pinfunction "1_1") (pintype "passive"))
      (node (ref "C24") (pin "2") (pinfunction "N_2") (pintype "passive"))
      (node (ref "C25") (pin "1") (pinfunction "1_1") (pintype "passive"))
      (node (ref "C26") (pin "1") (pinfunction "1_1") (pintype "passive"))
      (node (ref "C28") (pin "2") (pinfunction "2_2") (pintype "passive"))
      (node (ref "C3") (pin "2") (pinfunction "2_2") (pintype "passive"))
      (node (ref "C4") (pin "1") (pinfunction "1_1") (pintype "passive"))
      (node (ref "C5") (pin "1") (pinfunction "1_1") (pintype "passive"))
      (node (ref "C6") (pin "1") (pinfunction "1_1") (pintype "passive"))
      (node (ref "C7") (pin "2") (pinfunction "2_2") (pintype "passive"))
      (node (ref "C8") (pin "1") (pinfunction "1_1") (pintype "passive"))
      (node (ref "C9") (pin "1") (pinfunction "1_1") (pintype "passive"))
      (node (ref "DD1") (pin "23") (pinfunction "VSS_23") (pintype "passive"))
      (node (ref "DD1") (pin "47") (pinfunction "VSS_47") (pintype "passive"))
      (node (ref "DD1") (pin "8") (pinfunction "VSSA_8") (pintype "passive"))
      (node (ref "DD2") (pin "5") (pinfunction "GND_5") (pintype "passive"))
      (node (ref "DD3") (pin "4") (pinfunction "GND_4") (pintype "power_in"))
      (node (ref "DD4") (pin "4") (pinfunction "GND_4") (pintype "passive"))
      (node (ref "DD4") (pin "9") (pinfunction "PAD_9") (pintype "passive"))
      (node (ref "DD5") (pin "4") (pinfunction "GND_4") (pintype "passive"))
      (node (ref "DD5") (pin "9") (pinfunction "PAD_9") (pintype "passive"))
      (node (ref "P1") (pin "3") (pinfunction "3_3") (pintype "passive"))
      (node (ref "P1") (pin "5") (pinfunction "5_5") (pintype "passive"))
      (node (ref "P1") (pin "9") (pinfunction "9_9") (pintype "passive"))
      (node (ref "P2") (pin "3") (pinfunction "3_3") (pintype "passive"))
      (node (ref "P2") (pin "5") (pinfunction "5_5") (pintype "passive"))
      (node (ref "P2") (pin "9") (pinfunction "9_9") (pintype "passive"))
      (node (ref "R11") (pin "2") (pinfunction "2_2") (pintype "passive"))
      (node (ref "R16") (pin "1") (pinfunction "1_1") (pintype "passive"))
      (node (ref "R7") (pin "1") (pinfunction "1_1") (pintype "passive"))
      (node (ref "R8") (pin "2") (pinfunction "2_2") (pintype "passive"))
      (node (ref "SW1") (pin "2") (pinfunction "NO_1_2") (pintype "passive"))
      (node (ref "SW1") (pin "3") (pinfunction "NO_2_3") (pintype "passive"))
      (node (ref "SW1") (pin "4") (pinfunction "NO_3_4") (pintype "passive"))
      (node (ref "SW2") (pin "2") (pinfunction "NO_1_2") (pintype "passive"))
      (node (ref "SW2") (pin "3") (pinfunction "NO_2_3") (pintype "passive"))
      (node (ref "SW2") (pin "4") (pinfunction "NO_3_4") (pintype "passive"))
      (node (ref "TP9") (pin "1") (pinfunction "1_1") (pintype "passive"))
      (node (ref "VD1") (pin "3") (pinfunction "3_3") (pintype "passive"))
      (node (ref "VD3") (pin "2") (pinfunction "2_2") (pintype "passive"))
      (node (ref "VD4") (pin "2") (pinfunction "2_2") (pintype "passive"))
      (node (ref "VD5") (pin "2") (pinfunction "2_2") (pintype "passive"))
      (node (ref "VD6") (pin "2") (pinfunction "A_2") (pintype "passive"))
      (node (ref "X1") (pin "2") (pinfunction "2_2") (pintype "passive"))
      (node (ref "X1") (pin "P1") (pinfunction "P1_P1") (pintype "passive"))
      (node (ref "X1") (pin "P2") (pinfunction "P2_P2") (pintype "passive"))
      (node (ref "X2") (pin "2") (pinfunction "2_2") (pintype "passive"))
      (node (ref "X2") (pin "P1") (pinfunction "P1_P1") (pintype "passive"))
      (node (ref "X2") (pin "P2") (pinfunction "P2_P2") (pintype "passive"))
      (node (ref "X3") (pin "P1") (pinfunction "P1_P1") (pintype "passive"))
      (node (ref "X3") (pin "P2") (pinfunction "P2_P2") (pintype "passive"))
      (node (ref "X4") (pin "1") (pinfunction "1_1") (pintype "passive"))
      (node (ref "Z1") (pin "2") (pintype "passive"))
      (node (ref "Z1") (pin "4") (pintype "passive"))
    )
    (net (code "40") (name "Net-(DD2-A)") (class "Default")
      (node (ref "DD2") (pin "6") (pinfunction "A_6") (pintype "passive"))
      (node (ref "R5") (pin "1") (pinfunction "1_1") (pintype "passive"))
    )
    (net (code "41") (name "Net-(DD2-B)") (class "Default")
      (node (ref "DD2") (pin "7") (pinfunction "B_7") (pintype "passive"))
      (node (ref "R6") (pin "1") (pinfunction "1_1") (pintype "passive"))
    )
    (net (code "42") (name "Net-(DD3-BST)") (class "Default")
      (node (ref "C13") (pin "2") (pinfunction "2_2") (pintype "passive"))
      (node (ref "DD3") (pin "6") (pinfunction "BST_6") (pintype "passive"))
    )
    (net (code "43") (name "Net-(DD3-SW)") (class "Default")
      (node (ref "C13") (pin "1") (pinfunction "1_1") (pintype "passive"))
      (node (ref "DD3") (pin "5") (pinfunction "SW_5") (pintype "passive"))
      (node (ref "L1") (pin "1") (pinfunction "1_1") (pintype "passive"))
    )
    (net (code "44") (name "Net-(R1-Pad2)") (class "Default")
      (node (ref "R1") (pin "2") (pinfunction "2_2") (pintype "passive"))
      (node (ref "R2") (pin "1") (pinfunction "1_1") (pintype "passive"))
    )
    (net (code "45") (name "Net-(R4-Pad1)") (class "Default")
      (node (ref "R4") (pin "1") (pinfunction "1_1") (pintype "passive"))
      (node (ref "R7") (pin "2") (pinfunction "2_2") (pintype "passive"))
    )
    (net (code "46") (name "Net-(R15-Pad1)") (class "Default")
      (node (ref "R15") (pin "1") (pinfunction "1_1") (pintype "passive"))
      (node (ref "X1") (pin "5") (pinfunction "5_5") (pintype "passive"))
    )
    (net (code "47") (name "Net-(VD2-BLUE_CATHODE)") (class "Default")
      (node (ref "R12") (pin "2") (pinfunction "2_2") (pintype "passive"))
      (node (ref "VD2") (pin "2") (pinfunction "BLUE_CATHODE_2") (pintype "passive"))
    )
    (net (code "48") (name "Net-(VD2-GREEN_CATHODE)") (class "Default")
      (node (ref "R13") (pin "2") (pinfunction "2_2") (pintype "passive"))
      (node (ref "VD2") (pin "3") (pinfunction "GREEN_CATHODE_3") (pintype "passive"))
    )
    (net (code "49") (name "Net-(VD2-RED_CATHODE)") (class "Default")
      (node (ref "R14") (pin "2") (pinfunction "2_2") (pintype "passive"))
      (node (ref "VD2") (pin "4") (pinfunction "RED_CATHODE_4") (pintype "passive"))
    )
    (net (code "50") (name "unconnected-(DD1-PB2-Pad20)") (class "Default")
      (node (ref "DD1") (pin "20") (pinfunction "PB2_20") (pintype "passive+no_connect"))
    )
    (net (code "51") (name "unconnected-(DD1-PB8-Pad45)") (class "Default")
      (node (ref "DD1") (pin "45") (pinfunction "PB8_45") (pintype "passive+no_connect"))
    )
    (net (code "52") (name "unconnected-(DD1-PB9-Pad46)") (class "Default")
      (node (ref "DD1") (pin "46") (pinfunction "PB9_46") (pintype "passive+no_connect"))
    )
    (net (code "53") (name "unconnected-(DD1-PB10-Pad21)") (class "Default")
      (node (ref "DD1") (pin "21") (pinfunction "PB10_21") (pintype "passive+no_connect"))
    )
    (net (code "54") (name "unconnected-(DD1-PB11-Pad22)") (class "Default")
      (node (ref "DD1") (pin "22") (pinfunction "PB11_22") (pintype "passive+no_connect"))
    )
    (net (code "55") (name "unconnected-(DD1-PB12-Pad25)") (class "Default")
      (node (ref "DD1") (pin "25") (pinfunction "PB12_25") (pintype "passive+no_connect"))
    )
    (net (code "56") (name "unconnected-(DD1-PB13-Pad26)") (class "Default")
      (node (ref "DD1") (pin "26") (pinfunction "PB13_26") (pintype "passive+no_connect"))
    )
    (net (code "57") (name "unconnected-(DD1-PB14-Pad27)") (class "Default")
      (node (ref "DD1") (pin "27") (pinfunction "PB14_27") (pintype "passive+no_connect"))
    )
    (net (code "58") (name "unconnected-(DD1-PB15-Pad28)") (class "Default")
      (node (ref "DD1") (pin "28") (pinfunction "PB15_28") (pintype "passive+no_connect"))
    )
    (net (code "59") (name "unconnected-(DD1-PC13-Pad2)") (class "Default")
      (node (ref "DD1") (pin "2") (pinfunction "PC13_2") (pintype "passive+no_connect"))
    )
    (net (code "60") (name "unconnected-(DD1-PC14-Pad3)") (class "Default")
      (node (ref "DD1") (pin "3") (pinfunction "PC14_3") (pintype "passive+no_connect"))
    )
    (net (code "61") (name "unconnected-(DD1-PC15-Pad4)") (class "Default")
      (node (ref "DD1") (pin "4") (pinfunction "PC15_4") (pintype "passive+no_connect"))
    )
    (net (code "62") (name "unconnected-(DD1-PF6-Pad35)") (class "Default")
      (node (ref "DD1") (pin "35") (pinfunction "PF6_35") (pintype "passive+no_connect"))
    )
    (net (code "63") (name "unconnected-(DD1-PF7-Pad36)") (class "Default")
      (node (ref "DD1") (pin "36") (pinfunction "PF7_36") (pintype "passive+no_connect"))
    )
    (net (code "64") (name "unconnected-(FID1-2-PadFID)") (class "Default")
      (node (ref "FID1") (pin "FID") (pinfunction "2_FID") (pintype "passive"))
    )
    (net (code "65") (name "unconnected-(FID2-2-PadFID)") (class "Default")
      (node (ref "FID2") (pin "FID") (pinfunction "2_FID") (pintype "passive"))
    )
    (net (code "66") (name "unconnected-(FID3-2-PadFID)") (class "Default")
      (node (ref "FID3") (pin "FID") (pinfunction "2_FID") (pintype "passive"))
    )
    (net (code "67") (name "unconnected-(P1-Pad6)") (class "Default")
      (node (ref "P1") (pin "6") (pinfunction "6_6") (pintype "passive+no_connect"))
    )
    (net (code "68") (name "unconnected-(P1-Pad7)") (class "Default")
      (node (ref "P1") (pin "7") (pinfunction "7_7") (pintype "passive+no_connect"))
    )
    (net (code "69") (name "unconnected-(P1-Pad8)") (class "Default")
      (node (ref "P1") (pin "8") (pinfunction "8_8") (pintype "passive+no_connect"))
    )
    (net (code "70") (name "unconnected-(P2-Pad6)") (class "Default")
      (node (ref "P2") (pin "6") (pinfunction "6_6") (pintype "passive+no_connect"))
    )
    (net (code "71") (name "unconnected-(P2-Pad7)") (class "Default")
      (node (ref "P2") (pin "7") (pinfunction "7_7") (pintype "passive+no_connect"))
    )
    (net (code "72") (name "unconnected-(P2-Pad8)") (class "Default")
      (node (ref "P2") (pin "8") (pinfunction "8_8") (pintype "passive+no_connect"))
    )
  )
)
